# mkrd-001.net
KiCad netlist of a schematic drawn in EAGLE
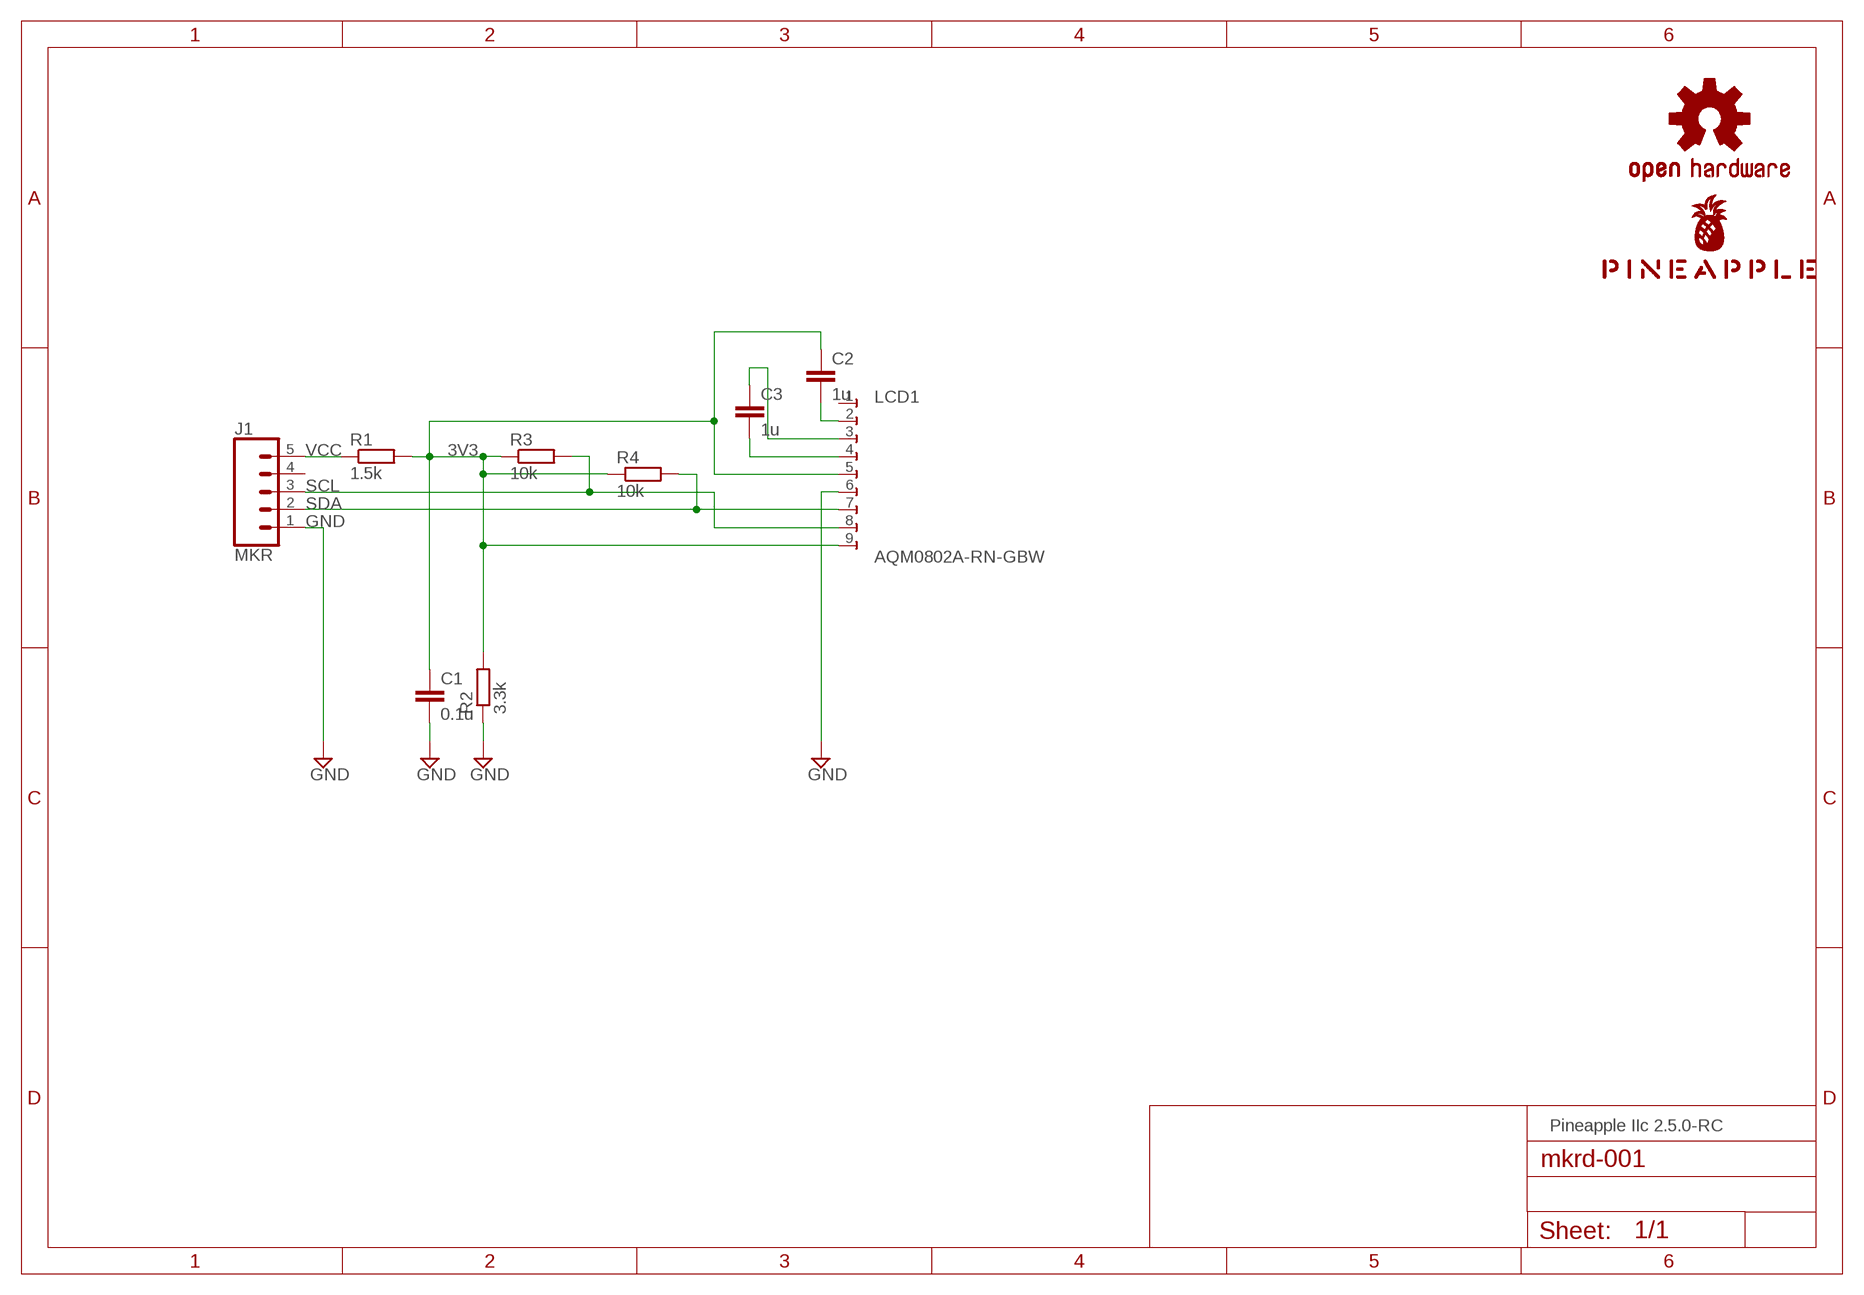
[diagram p0: schematic, sheet 1]

(export (version "E")
  (design (tool "Eeschema 10.0.6"))
  (components
    (comp (ref "C1")
      (value "0.1u")
      (footprint "eagle-import:C025-024X044")
      (libsource (lib "eagle-import") (part "C-EU025-024X044"))
    )
    (comp (ref "C2")
      (value "1u")
      (footprint "eagle-import:C025-025X050")
      (libsource (lib "eagle-import") (part "C-EU025-025X050"))
    )
    (comp (ref "C3")
      (value "1u")
      (footprint "eagle-import:C025-025X050")
      (libsource (lib "eagle-import") (part "C-EU025-025X050"))
    )
    (comp (ref "J1")
      (value "MKR")
      (footprint "eagle-import:JST-5-PTH")
      (libsource (lib "eagle-import") (part "CONN_05JST"))
    )
    (comp (ref "LCD1")
      (value "AQM0802A-RN-GBW")
      (footprint "eagle-import:AQM0802A-RN-GBW-FOOTPRINT")
      (libsource (lib "eagle-import") (part "AQM0802A-RN-GBW"))
    )
    (comp (ref "LOGO1")
      (value "OSHW-LOGOS-COPPER")
      (footprint "eagle-import:OSHW-LOGO-S_COPPER")
      (libsource (lib "eagle-import") (part "OSHW-LOGOS-COPPER"))
    )
    (comp (ref "R1")
      (value "1.5k")
      (footprint "eagle-import:0204_5")
      (libsource (lib "eagle-import") (part "R-EU_0204/5"))
    )
    (comp (ref "R2")
      (value "3.3k")
      (footprint "eagle-import:0204_5")
      (libsource (lib "eagle-import") (part "R-EU_0204/5"))
    )
    (comp (ref "R3")
      (value "10k")
      (footprint "eagle-import:0204_5")
      (libsource (lib "eagle-import") (part "R-EU_0204/5"))
    )
    (comp (ref "R4")
      (value "10k")
      (footprint "eagle-import:0204_5")
      (libsource (lib "eagle-import") (part "R-EU_0204/5"))
    )
    (comp (ref "U$1")
      (value "PINEAPPLE450_SILK")
      (footprint "eagle-import:PINEAPPLE450_SILK")
      (libsource (lib "eagle-import") (part "PINEAPPLE450_SILK"))
    )
  )
  (nets
    (net (code "1") (name "/3V3") (class "Default")
      (node (ref "C1") (pin "1") (pinfunction "1_1") (pintype "passive"))
      (node (ref "C2") (pin "1") (pinfunction "1_1") (pintype "passive"))
      (node (ref "LCD1") (pin "5") (pinfunction "5_5") (pintype "passive"))
      (node (ref "LCD1") (pin "9") (pinfunction "9_9") (pintype "passive"))
      (node (ref "R1") (pin "2") (pinfunction "2_2") (pintype "passive"))
      (node (ref "R2") (pin "2") (pinfunction "2_2") (pintype "passive"))
      (node (ref "R3") (pin "1") (pinfunction "1_1") (pintype "passive"))
      (node (ref "R4") (pin "1") (pinfunction "1_1") (pintype "passive"))
    )
    (net (code "2") (name "/SCL") (class "Default")
      (node (ref "J1") (pin "3") (pinfunction "3_3") (pintype "passive"))
      (node (ref "LCD1") (pin "8") (pinfunction "8_8") (pintype "passive"))
      (node (ref "R3") (pin "2") (pinfunction "2_2") (pintype "passive"))
    )
    (net (code "3") (name "/SDA") (class "Default")
      (node (ref "J1") (pin "2") (pinfunction "2_2") (pintype "passive"))
      (node (ref "LCD1") (pin "7") (pinfunction "7_7") (pintype "passive"))
      (node (ref "R4") (pin "2") (pinfunction "2_2") (pintype "passive"))
    )
    (net (code "4") (name "/VCC") (class "Default")
      (node (ref "J1") (pin "5") (pinfunction "5_5") (pintype "passive"))
      (node (ref "R1") (pin "1") (pinfunction "1_1") (pintype "passive"))
    )
    (net (code "5") (name "GND") (class "Default")
      (node (ref "C1") (pin "2") (pinfunction "2_2") (pintype "passive"))
      (node (ref "J1") (pin "1") (pinfunction "1_1") (pintype "passive"))
      (node (ref "LCD1") (pin "6") (pinfunction "6_6") (pintype "passive"))
      (node (ref "R2") (pin "1") (pinfunction "1_1") (pintype "passive"))
    )
    (net (code "6") (name "Net-(C2-Pad2)") (class "Default")
      (node (ref "C2") (pin "2") (pinfunction "2_2") (pintype "passive"))
      (node (ref "LCD1") (pin "2") (pinfunction "2_2") (pintype "passive"))
    )
    (net (code "7") (name "Net-(C3-Pad1)") (class "Default")
      (node (ref "C3") (pin "1") (pinfunction "1_1") (pintype "passive"))
      (node (ref "LCD1") (pin "3") (pinfunction "3_3") (pintype "passive"))
    )
    (net (code "8") (name "Net-(C3-Pad2)") (class "Default")
      (node (ref "C3") (pin "2") (pinfunction "2_2") (pintype "passive"))
      (node (ref "LCD1") (pin "4") (pinfunction "4_4") (pintype "passive"))
    )
    (net (code "9") (name "unconnected-(J1-Pad4)") (class "Default")
      (node (ref "J1") (pin "4") (pinfunction "4_4") (pintype "passive"))
    )
    (net (code "10") (name "unconnected-(LCD1-Pad1)") (class "Default")
      (node (ref "LCD1") (pin "1") (pinfunction "1_1") (pintype "passive"))
    )
  )
)
